# LED_Mirror_555.net
KiCad netlist of a schematic drawn in EAGLE
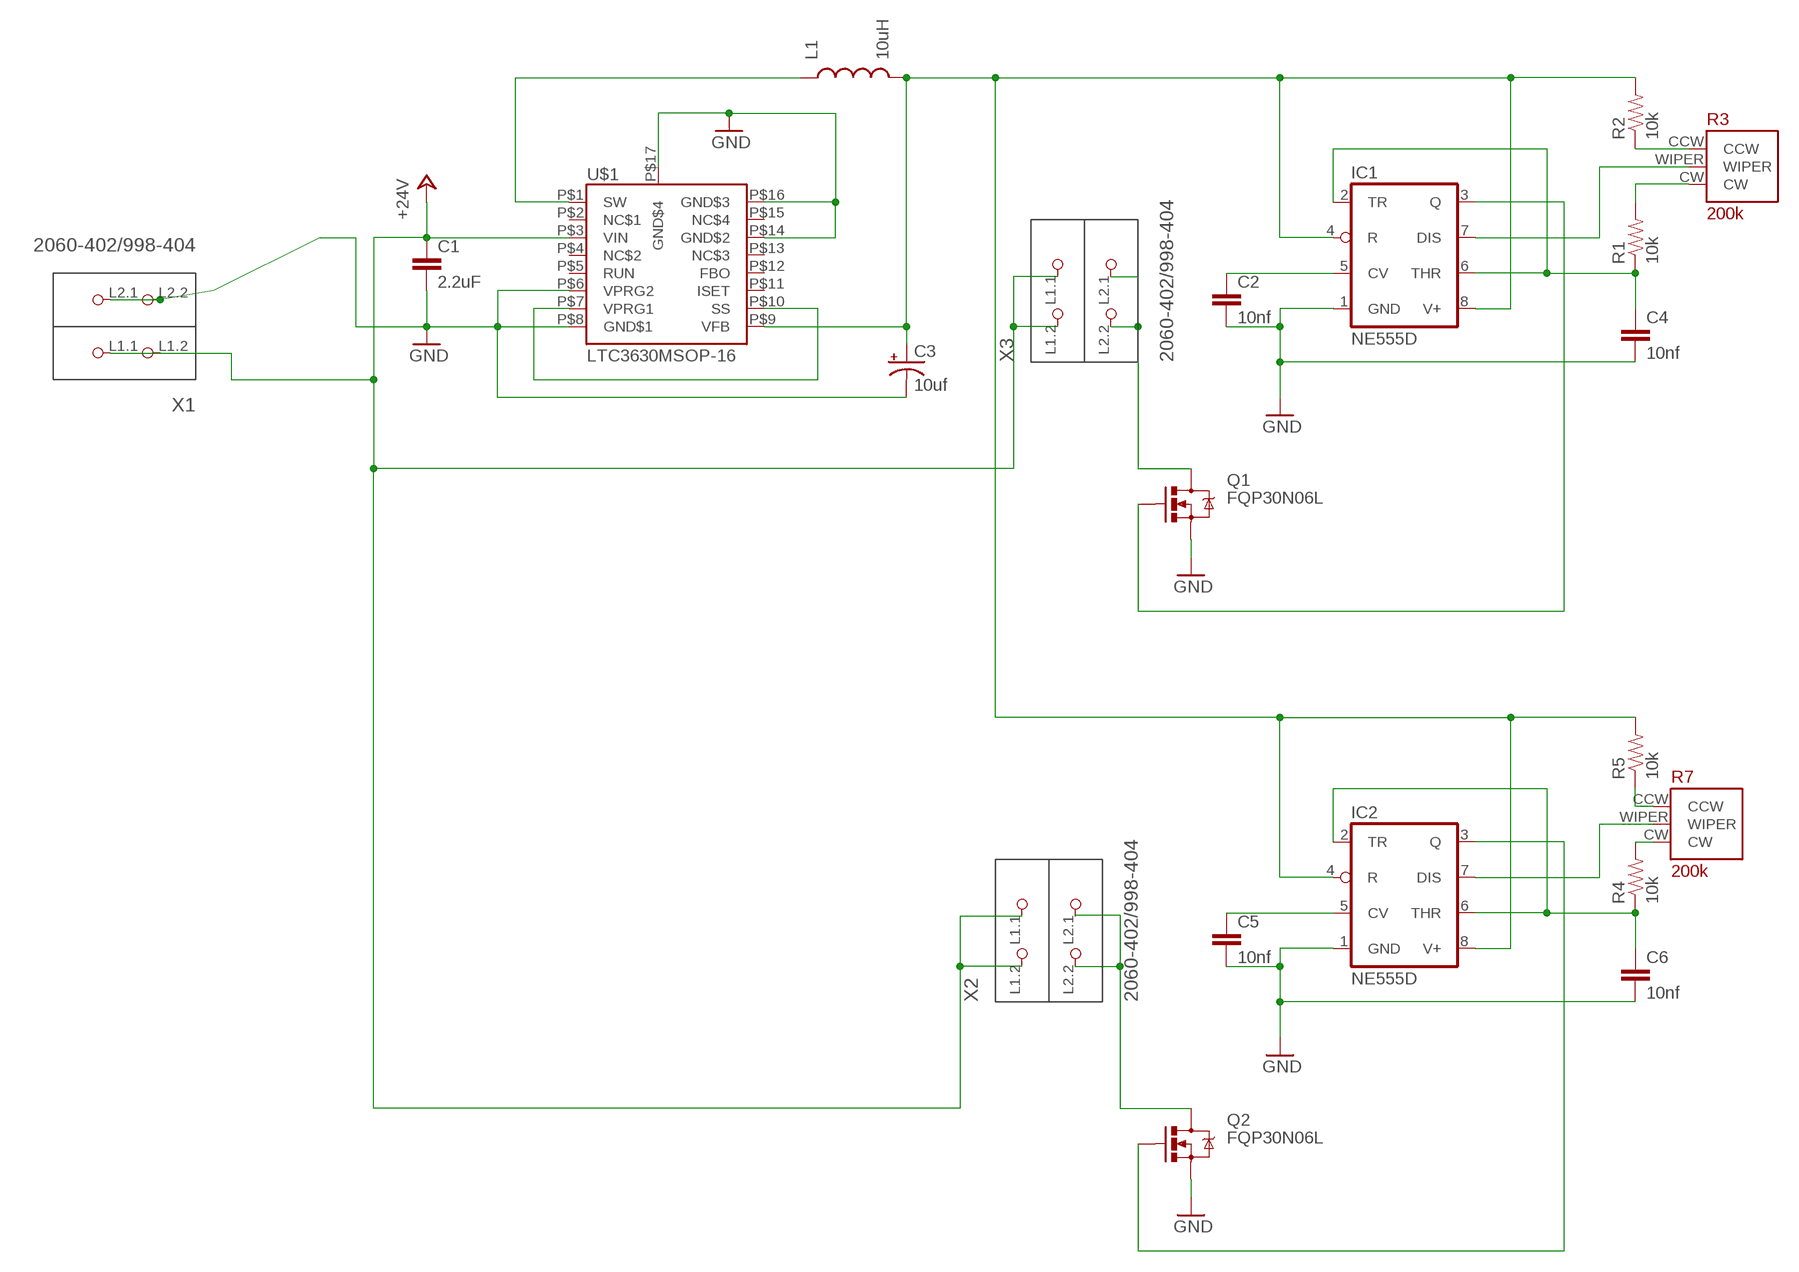
[diagram p0: schematic, sheet 1]

(export (version "E")
  (design (tool "Eeschema 10.0.6"))
  (components
    (comp (ref "C1")
      (value "2.2uF")
      (footprint "eagle-import:0805")
      (libsource (lib "eagle-import") (part "CAP0805"))
    )
    (comp (ref "C2")
      (value "10nf")
      (footprint "eagle-import:0805")
      (libsource (lib "eagle-import") (part "CAP0805"))
    )
    (comp (ref "C3")
      (value "10uf")
      (footprint "eagle-import:EIA3216")
      (libsource (lib "eagle-import") (part "CAP_POL1206"))
    )
    (comp (ref "C4")
      (value "10nf")
      (footprint "eagle-import:0805")
      (libsource (lib "eagle-import") (part "CAP0805"))
    )
    (comp (ref "C5")
      (value "10nf")
      (footprint "eagle-import:0805")
      (libsource (lib "eagle-import") (part "CAP0805"))
    )
    (comp (ref "C6")
      (value "10nf")
      (footprint "eagle-import:0805")
      (libsource (lib "eagle-import") (part "CAP0805"))
    )
    (comp (ref "IC1")
      (value "NE555D")
      (footprint "eagle-import:SO08")
      (libsource (lib "eagle-import") (part "555DNE"))
    )
    (comp (ref "IC2")
      (value "NE555D")
      (footprint "eagle-import:SO08")
      (libsource (lib "eagle-import") (part "555DNE"))
    )
    (comp (ref "L1")
      (value "10uH")
      (footprint "eagle-import:NPI75C")
      (libsource (lib "eagle-import") (part "INDUCTORNPI75"))
    )
    (comp (ref "Q1")
      (value "FQP30N06L")
      (footprint "eagle-import:TO220V")
      (libsource (lib "eagle-import") (part "MOSFET-NCHANNELFQP30N06L"))
    )
    (comp (ref "Q2")
      (value "FQP30N06L")
      (footprint "eagle-import:TO220V")
      (libsource (lib "eagle-import") (part "MOSFET-NCHANNELFQP30N06L"))
    )
    (comp (ref "R1")
      (value "10k")
      (footprint "eagle-import:0805")
      (libsource (lib "eagle-import") (part "RESISTOR0805-RES"))
    )
    (comp (ref "R2")
      (value "10k")
      (footprint "eagle-import:0805")
      (libsource (lib "eagle-import") (part "RESISTOR0805-RES"))
    )
    (comp (ref "R3")
      (value "200k")
      (footprint "eagle-import:TRIMPOT_3296_SMD")
      (libsource (lib "eagle-import") (part "TRIMPOT_3296W_SMD"))
    )
    (comp (ref "R4")
      (value "10k")
      (footprint "eagle-import:0805")
      (libsource (lib "eagle-import") (part "RESISTOR0805-RES"))
    )
    (comp (ref "R5")
      (value "10k")
      (footprint "eagle-import:0805")
      (libsource (lib "eagle-import") (part "RESISTOR0805-RES"))
    )
    (comp (ref "R7")
      (value "200k")
      (footprint "eagle-import:TRIMPOT_3296_SMD")
      (libsource (lib "eagle-import") (part "TRIMPOT_3296W_SMD"))
    )
    (comp (ref "U$1")
      (value "LTC3630MSOP-16")
      (footprint "eagle-import:MSOP-16")
      (libsource (lib "eagle-import") (part "LTC3630MSOP-16"))
    )
    (comp (ref "X1")
      (value "2060-402/998-404")
      (footprint "eagle-import:P-2060-402_998-404")
      (libsource (lib "eagle-import") (part "2060-402/998-404"))
    )
    (comp (ref "X2")
      (value "2060-402/998-404")
      (footprint "eagle-import:P-2060-402_998-404")
      (libsource (lib "eagle-import") (part "2060-402/998-404"))
    )
    (comp (ref "X3")
      (value "2060-402/998-404")
      (footprint "eagle-import:P-2060-402_998-404")
      (libsource (lib "eagle-import") (part "2060-402/998-404"))
    )
  )
  (nets
    (net (code "1") (name "+24V") (class "Default")
      (node (ref "C1") (pin "1") (pinfunction "1_1") (pintype "passive"))
      (node (ref "U$1") (pin "P$3") (pinfunction "VIN_P$3") (pintype "power_in"))
      (node (ref "X1") (pin "L1.1") (pinfunction "P1.1_L1.1") (pintype "bidirectional"))
      (node (ref "X1") (pin "L1.2") (pinfunction "P1.2_L1.2") (pintype "bidirectional"))
      (node (ref "X2") (pin "L1.1") (pinfunction "P1.1_L1.1") (pintype "bidirectional"))
      (node (ref "X2") (pin "L1.2") (pinfunction "P1.2_L1.2") (pintype "bidirectional"))
      (node (ref "X3") (pin "L1.1") (pinfunction "P1.1_L1.1") (pintype "bidirectional"))
      (node (ref "X3") (pin "L1.2") (pinfunction "P1.2_L1.2") (pintype "bidirectional"))
    )
    (net (code "2") (name "GND") (class "Default")
      (node (ref "C1") (pin "2") (pinfunction "2_2") (pintype "passive"))
      (node (ref "C2") (pin "2") (pinfunction "2_2") (pintype "passive"))
      (node (ref "C3") (pin "C") (pinfunction "-_C") (pintype "passive"))
      (node (ref "C4") (pin "2") (pinfunction "2_2") (pintype "passive"))
      (node (ref "C5") (pin "2") (pinfunction "2_2") (pintype "passive"))
      (node (ref "C6") (pin "2") (pinfunction "2_2") (pintype "passive"))
      (node (ref "IC1") (pin "1") (pinfunction "GND_1") (pintype "power_in"))
      (node (ref "IC2") (pin "1") (pinfunction "GND_1") (pintype "power_in"))
      (node (ref "Q1") (pin "3") (pinfunction "S_3") (pintype "passive"))
      (node (ref "Q2") (pin "3") (pinfunction "S_3") (pintype "passive"))
      (node (ref "U$1") (pin "P$14") (pinfunction "GND$2_P$14") (pintype "power_in"))
      (node (ref "U$1") (pin "P$16") (pinfunction "GND$3_P$16") (pintype "power_in"))
      (node (ref "U$1") (pin "P$17") (pinfunction "GND$4_P$17") (pintype "power_in"))
      (node (ref "U$1") (pin "P$6") (pinfunction "VPRG2_P$6") (pintype "input"))
      (node (ref "U$1") (pin "P$8") (pinfunction "GND$1_P$8") (pintype "power_in"))
      (node (ref "X1") (pin "L2.1") (pinfunction "P2.1_L2.1") (pintype "bidirectional"))
      (node (ref "X1") (pin "L2.2") (pinfunction "P2.2_L2.2") (pintype "bidirectional"))
    )
    (net (code "3") (name "Net-(C3-+)") (class "Default")
      (node (ref "C3") (pin "A") (pinfunction "+_A") (pintype "passive"))
      (node (ref "IC1") (pin "4") (pinfunction "R_4") (pintype "input"))
      (node (ref "IC1") (pin "8") (pinfunction "V+_8") (pintype "power_in"))
      (node (ref "IC2") (pin "4") (pinfunction "R_4") (pintype "input"))
      (node (ref "IC2") (pin "8") (pinfunction "V+_8") (pintype "power_in"))
      (node (ref "L1") (pin "2") (pinfunction "2_2") (pintype "passive"))
      (node (ref "R2") (pin "2") (pinfunction "2_2") (pintype "passive"))
      (node (ref "R5") (pin "2") (pinfunction "2_2") (pintype "passive"))
      (node (ref "U$1") (pin "P$9") (pinfunction "VFB_P$9") (pintype "input"))
    )
    (net (code "4") (name "Net-(IC1-CV)") (class "Default")
      (node (ref "C2") (pin "1") (pinfunction "1_1") (pintype "passive"))
      (node (ref "IC1") (pin "5") (pinfunction "CV_5") (pintype "input"))
    )
    (net (code "5") (name "Net-(IC1-DIS)") (class "Default")
      (node (ref "IC1") (pin "7") (pinfunction "DIS_7") (pintype "input"))
      (node (ref "R3") (pin "WIPER") (pinfunction "WIPER_WIPER") (pintype "bidirectional"))
    )
    (net (code "6") (name "Net-(IC1-Q)") (class "Default")
      (node (ref "IC1") (pin "3") (pinfunction "Q_3") (pintype "output"))
      (node (ref "Q1") (pin "1") (pinfunction "G_1") (pintype "passive"))
    )
    (net (code "7") (name "Net-(IC1-THR)") (class "Default")
      (node (ref "C4") (pin "1") (pinfunction "1_1") (pintype "passive"))
      (node (ref "IC1") (pin "2") (pinfunction "TR_2") (pintype "input"))
      (node (ref "IC1") (pin "6") (pinfunction "THR_6") (pintype "input"))
      (node (ref "R1") (pin "1") (pinfunction "1_1") (pintype "passive"))
    )
    (net (code "8") (name "Net-(IC2-CV)") (class "Default")
      (node (ref "C5") (pin "1") (pinfunction "1_1") (pintype "passive"))
      (node (ref "IC2") (pin "5") (pinfunction "CV_5") (pintype "input"))
    )
    (net (code "9") (name "Net-(IC2-DIS)") (class "Default")
      (node (ref "IC2") (pin "7") (pinfunction "DIS_7") (pintype "input"))
      (node (ref "R7") (pin "WIPER") (pinfunction "WIPER_WIPER") (pintype "bidirectional"))
    )
    (net (code "10") (name "Net-(IC2-Q)") (class "Default")
      (node (ref "IC2") (pin "3") (pinfunction "Q_3") (pintype "output"))
      (node (ref "Q2") (pin "1") (pinfunction "G_1") (pintype "passive"))
    )
    (net (code "11") (name "Net-(IC2-THR)") (class "Default")
      (node (ref "C6") (pin "1") (pinfunction "1_1") (pintype "passive"))
      (node (ref "IC2") (pin "2") (pinfunction "TR_2") (pintype "input"))
      (node (ref "IC2") (pin "6") (pinfunction "THR_6") (pintype "input"))
      (node (ref "R4") (pin "1") (pinfunction "1_1") (pintype "passive"))
    )
    (net (code "12") (name "Net-(Q1-D)") (class "Default")
      (node (ref "Q1") (pin "2") (pinfunction "D_2") (pintype "passive"))
      (node (ref "X3") (pin "L2.1") (pinfunction "P2.1_L2.1") (pintype "bidirectional"))
      (node (ref "X3") (pin "L2.2") (pinfunction "P2.2_L2.2") (pintype "bidirectional"))
    )
    (net (code "13") (name "Net-(Q2-D)") (class "Default")
      (node (ref "Q2") (pin "2") (pinfunction "D_2") (pintype "passive"))
      (node (ref "X2") (pin "L2.2") (pinfunction "P2.2_L2.2") (pintype "bidirectional"))
    )
    (net (code "14") (name "Net-(R1-Pad2)") (class "Default")
      (node (ref "R1") (pin "2") (pinfunction "2_2") (pintype "passive"))
      (node (ref "R3") (pin "CW") (pinfunction "CW_CW") (pintype "bidirectional"))
    )
    (net (code "15") (name "Net-(R2-Pad1)") (class "Default")
      (node (ref "R2") (pin "1") (pinfunction "1_1") (pintype "passive"))
      (node (ref "R3") (pin "CCW") (pinfunction "CCW_CCW") (pintype "bidirectional"))
    )
    (net (code "16") (name "Net-(R4-Pad2)") (class "Default")
      (node (ref "R4") (pin "2") (pinfunction "2_2") (pintype "passive"))
      (node (ref "R7") (pin "CW") (pinfunction "CW_CW") (pintype "bidirectional"))
    )
    (net (code "17") (name "Net-(R5-Pad1)") (class "Default")
      (node (ref "R5") (pin "1") (pinfunction "1_1") (pintype "passive"))
      (node (ref "R7") (pin "CCW") (pinfunction "CCW_CCW") (pintype "bidirectional"))
    )
    (net (code "18") (name "Net-(U$1-SS)") (class "Default")
      (node (ref "U$1") (pin "P$10") (pinfunction "SS_P$10") (pintype "input"))
      (node (ref "U$1") (pin "P$7") (pinfunction "VPRG1_P$7") (pintype "input"))
    )
    (net (code "19") (name "Net-(U$1-SW)") (class "Default")
      (node (ref "L1") (pin "1") (pinfunction "1_1") (pintype "passive"))
      (node (ref "U$1") (pin "P$1") (pinfunction "SW_P$1") (pintype "output"))
    )
    (net (code "20") (name "unconnected-(U$1-FBO-PadP$12)") (class "Default")
      (node (ref "U$1") (pin "P$12") (pinfunction "FBO_P$12") (pintype "output"))
    )
    (net (code "21") (name "unconnected-(U$1-ISET-PadP$11)") (class "Default")
      (node (ref "U$1") (pin "P$11") (pinfunction "ISET_P$11") (pintype "bidirectional"))
    )
    (net (code "22") (name "unconnected-(U$1-NC$1-PadP$2)") (class "Default")
      (node (ref "U$1") (pin "P$2") (pinfunction "NC$1_P$2") (pintype "no_connect"))
    )
    (net (code "23") (name "unconnected-(U$1-NC$2-PadP$4)") (class "Default")
      (node (ref "U$1") (pin "P$4") (pinfunction "NC$2_P$4") (pintype "no_connect"))
    )
    (net (code "24") (name "unconnected-(U$1-NC$3-PadP$13)") (class "Default")
      (node (ref "U$1") (pin "P$13") (pinfunction "NC$3_P$13") (pintype "bidirectional"))
    )
    (net (code "25") (name "unconnected-(U$1-NC$4-PadP$15)") (class "Default")
      (node (ref "U$1") (pin "P$15") (pinfunction "NC$4_P$15") (pintype "no_connect"))
    )
    (net (code "26") (name "unconnected-(U$1-RUN-PadP$5)") (class "Default")
      (node (ref "U$1") (pin "P$5") (pinfunction "RUN_P$5") (pintype "input"))
    )
    (net (code "27") (name "unconnected-(X2-P2.1-PadL2.1)") (class "Default")
      (node (ref "X2") (pin "L2.1") (pinfunction "P2.1_L2.1") (pintype "bidirectional"))
    )
  )
)
